# Power.net
KiCad netlist of a schematic drawn in Altium Designer
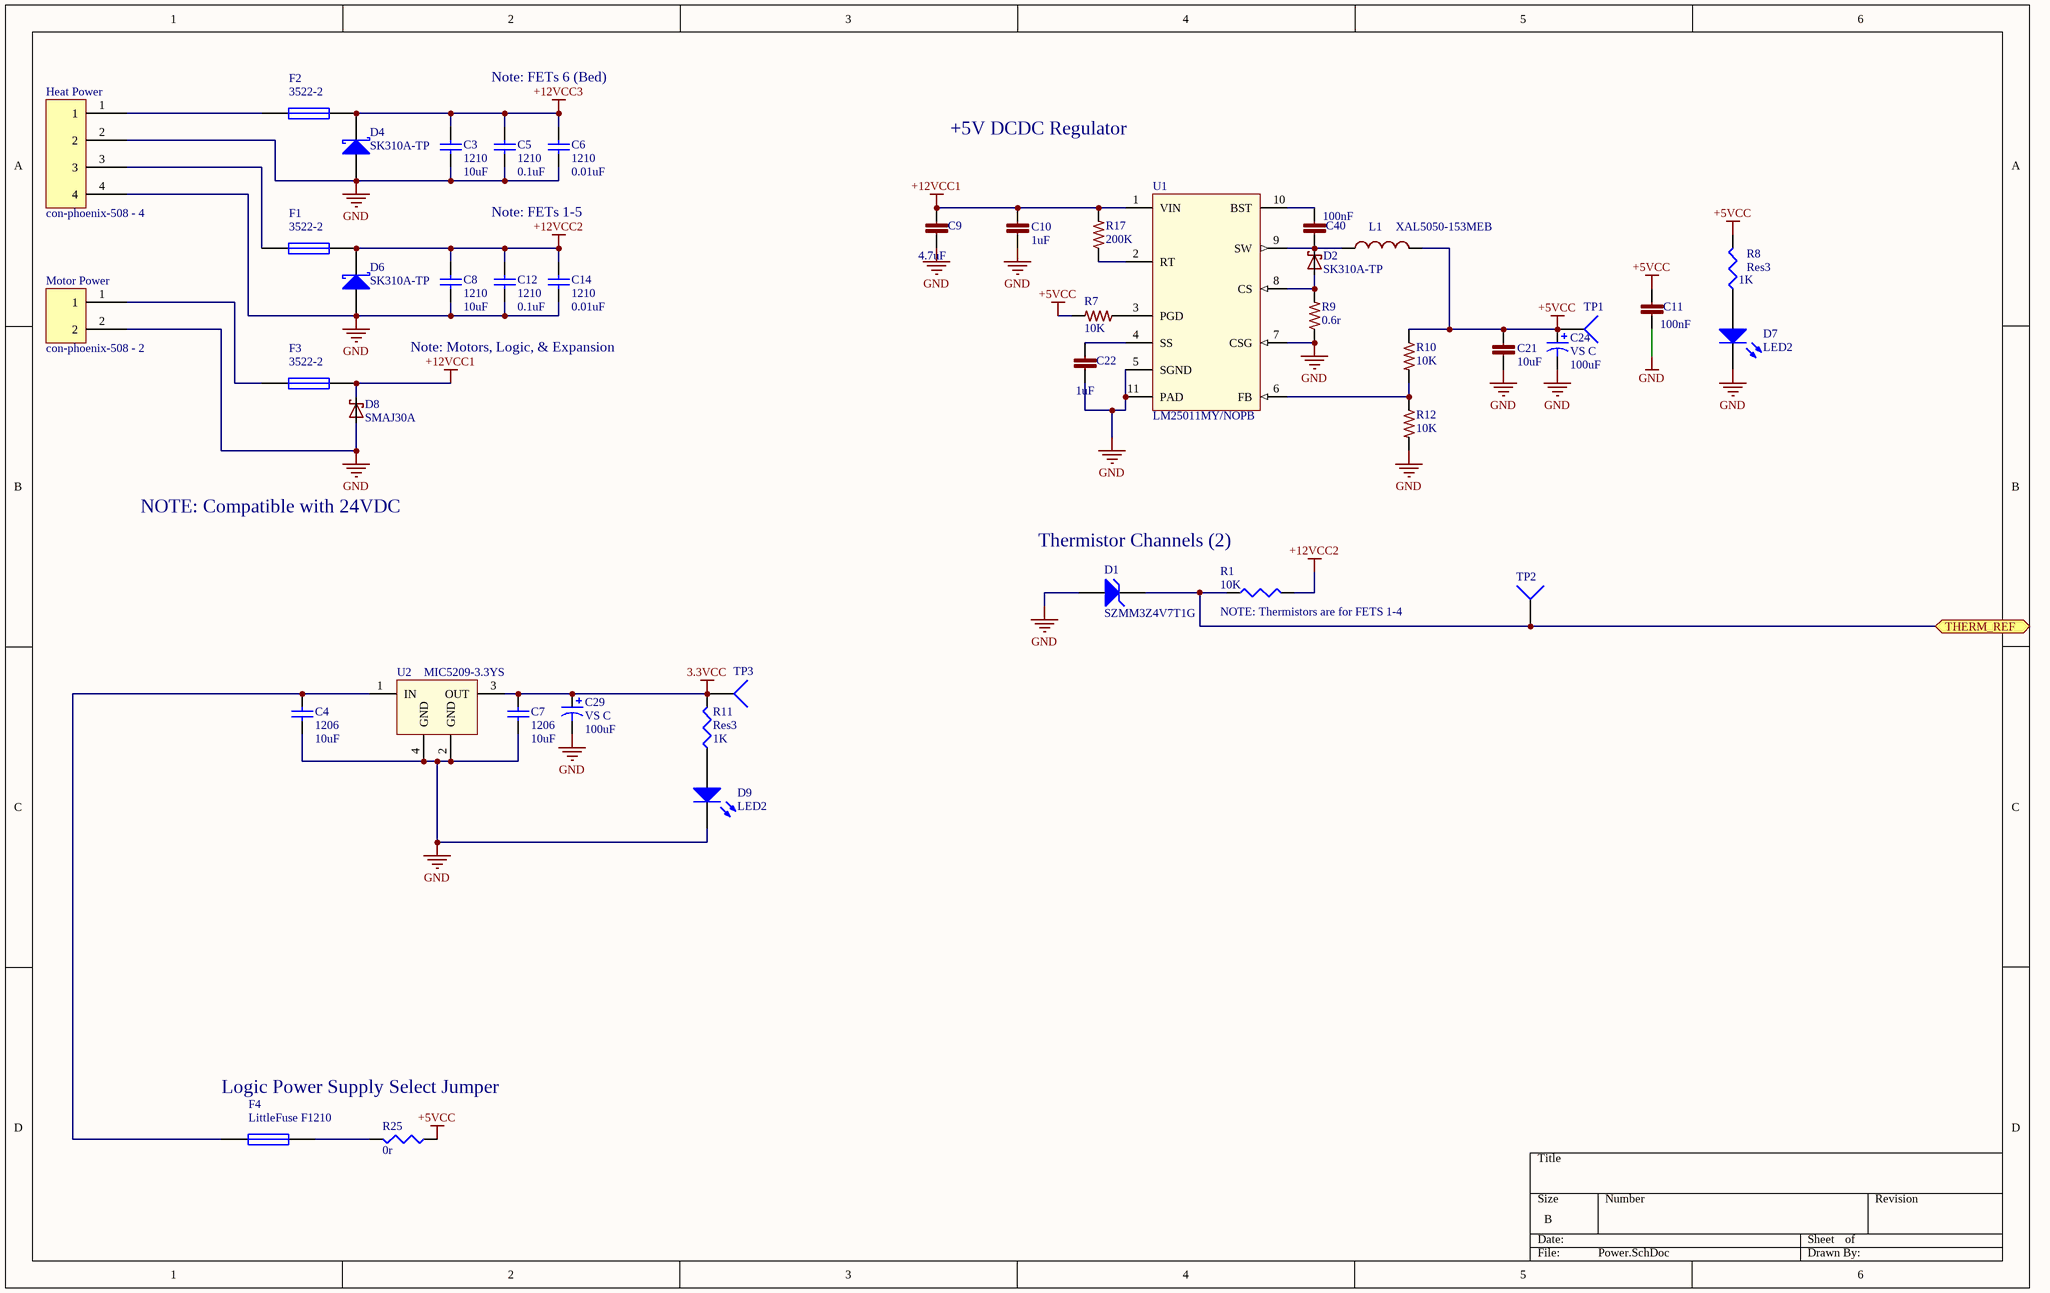
[diagram p0: Power.SchDoc]

(export (version "E")
  (design (tool "Eeschema 10.0.6"))
  (components
    (comp (ref "C3")
      (value "1210")
      (footprint "C1210")
      (description "Capacitor (Semiconductor SIM Model)")
      (fields (field (name "ALTIUM_VALUE") "10uF") (field (name "PUBLISHER") "Altium Limited"))
      (libsource (lib "Miscellaneous Devices") (part "Cap Semi"))
    )
    (comp (ref "C4")
      (value "1206")
      (footprint "C1206")
      (description "Capacitor (Semiconductor SIM Model)")
      (fields (field (name "ALTIUM_VALUE") "10uF") (field (name "PUBLISHER") "Altium Limited"))
      (libsource (lib "Miscellaneous Devices") (part "Cap Semi"))
    )
    (comp (ref "C5")
      (value "1210")
      (footprint "C1210")
      (description "Capacitor (Semiconductor SIM Model)")
      (fields (field (name "ALTIUM_VALUE") "0.1uF") (field (name "PUBLISHER") "Altium Limited"))
      (libsource (lib "Miscellaneous Devices") (part "Cap Semi"))
    )
    (comp (ref "C6")
      (value "1210")
      (footprint "C1210")
      (description "Capacitor (Semiconductor SIM Model)")
      (fields (field (name "ALTIUM_VALUE") "0.01uF") (field (name "PUBLISHER") "Altium Limited"))
      (libsource (lib "Miscellaneous Devices") (part "Cap Semi"))
    )
    (comp (ref "C7")
      (value "1206")
      (footprint "C1206")
      (description "Capacitor (Semiconductor SIM Model)")
      (fields (field (name "ALTIUM_VALUE") "10uF") (field (name "PUBLISHER") "Altium Limited"))
      (libsource (lib "Miscellaneous Devices") (part "Cap Semi"))
    )
    (comp (ref "C8")
      (value "1210")
      (footprint "C1210")
      (description "Capacitor (Semiconductor SIM Model)")
      (fields (field (name "ALTIUM_VALUE") "10uF") (field (name "PUBLISHER") "Altium Limited"))
      (libsource (lib "Miscellaneous Devices") (part "Cap Semi"))
    )
    (comp (ref "C9")
      (value "4.7uF")
      (footprint "C1206")
      (description "CAP CER 1206 4.7uF 50V 10% X5R")
      (fields
        (field (name "MANUFACTURERPARTNUMBER") "C1206C475K5PACTU")
        (field (name "PUBLISHER") "UltiMachine")
      )
      (libsource (lib "3Delight") (part "C1206C475K5PACTU"))
    )
    (comp (ref "C10")
      (value "1uF")
      (footprint "C0805")
      (description "CAP CER 0805 1uF 50V 10% X7R")
      (fields
        (field (name "MANUFACTURERPARTNUMBER") "GRM21BR71H105KA12L")
        (field (name "PUBLISHER") "UltiMachine")
      )
      (libsource (lib "3Delight") (part "GRM21BR71H105KA12L"))
    )
    (comp (ref "C11")
      (value "100nF")
      (footprint "C0603")
      (description "CAP CER 0603 100nF 50V 10% X7R")
      (fields
        (field (name "MANUFACTURERPARTNUMBER") "C0603C104K5RACTU")
        (field (name "PUBLISHER") "UltiMachine")
      )
      (libsource (lib "3Delight") (part "C0603C104K5RACTU"))
    )
    (comp (ref "C12")
      (value "1210")
      (footprint "C1210")
      (description "Capacitor (Semiconductor SIM Model)")
      (fields (field (name "ALTIUM_VALUE") "0.1uF") (field (name "PUBLISHER") "Altium Limited"))
      (libsource (lib "Miscellaneous Devices") (part "Cap Semi"))
    )
    (comp (ref "C14")
      (value "1210")
      (footprint "C1210")
      (description "Capacitor (Semiconductor SIM Model)")
      (fields (field (name "ALTIUM_VALUE") "0.01uF") (field (name "PUBLISHER") "Altium Limited"))
      (libsource (lib "Miscellaneous Devices") (part "Cap Semi"))
    )
    (comp (ref "C21")
      (value "10uF")
      (footprint "C0805")
      (description "CAP CER 0805 10uF 10V 10% X5R")
      (fields
        (field (name "MANUFACTURERPARTNUMBER") "C0805C106K8PACTU")
        (field (name "PUBLISHER") "UltiMachine")
      )
      (libsource (lib "3Delight") (part "C0805C106K8PACTU"))
    )
    (comp (ref "C22")
      (value "1uF")
      (footprint "C0402")
      (description "CAP CER 0402 1uF 6.3V 10% X5R")
      (fields
        (field (name "MANUFACTURERPARTNUMBER") "GRM155R60J105KE19D")
        (field (name "PUBLISHER") "UltiMachine")
      )
      (libsource (lib "3Delight") (part "GRM155R60J105KE19D"))
    )
    (comp (ref "C24")
      (value "VS C")
      (footprint "Panasonic VS C")
      (description "Polarized Capacitor (Surface Mount)")
      (fields (field (name "ALTIUM_VALUE") "100uF") (field (name "PUBLISHER") "Altium Limited"))
      (libsource (lib "Miscellaneous Devices") (part "Cap Pol3"))
    )
    (comp (ref "C29")
      (value "VS C")
      (footprint "Panasonic VS C")
      (description "Polarized Capacitor (Surface Mount)")
      (fields (field (name "ALTIUM_VALUE") "100uF") (field (name "PUBLISHER") "Altium Limited"))
      (libsource (lib "Miscellaneous Devices") (part "Cap Pol3"))
    )
    (comp (ref "C40")
      (value "100nF")
      (footprint "C0603")
      (description "CAP CER 0603 100nF 50V 10% X7R")
      (fields
        (field (name "MANUFACTURERPARTNUMBER") "C0603C104K5RACTU")
        (field (name "PUBLISHER") "UltiMachine")
      )
      (libsource (lib "3Delight") (part "C0603C104K5RACTU"))
    )
    (comp (ref "D1")
      (value "SZMM3Z4V7T1G")
      (footprint "SZMM3Z4V7T1G")
      (description "Zener Diode")
      (fields (field (name "PUBLISHER") "Altium Limited"))
      (libsource (lib "Miscellaneous Devices") (part "D Zener"))
    )
    (comp (ref "D2")
      (value "SK310A-TP")
      (footprint "SMA-SM")
      (description "DIODE Schottky 3A SMA")
      (fields (field (name "MANUFACTURERPARTNUMBER") "SK310A") (field (name "PUBLISHER") "UltiMachine"))
      (libsource (lib "3Delight") (part "SK310A"))
    )
    (comp (ref "D4")
      (value "SK310A-TP")
      (footprint "SK310A-TP")
      (description "Schottky Diode")
      (fields (field (name "PUBLISHER") "Altium Limited"))
      (libsource (lib "Miscellaneous Devices") (part "D Schottky"))
    )
    (comp (ref "D6")
      (value "SK310A-TP")
      (footprint "SK310A-TP")
      (description "Schottky Diode")
      (fields (field (name "PUBLISHER") "Altium Limited"))
      (libsource (lib "Miscellaneous Devices") (part "D Schottky"))
    )
    (comp (ref "D7")
      (value "LED2")
      (footprint "SM 0805 polarized")
      (description "Typical RED, GREEN, YELLOW, AMBER GaAs LED")
      (fields (field (name "PUBLISHER") "Altium Limited"))
      (libsource (lib "Miscellaneous Devices") (part "LED2"))
    )
    (comp (ref "D8")
      (value "SMAJ30A")
      (footprint "SMA-SM")
      (description "DIODE TVS 30V SMA")
      (fields (field (name "PUBLISHER") "UltiMachine"))
      (libsource (lib "ZMBo Schematic Library") (part "SMAJ30A"))
    )
    (comp (ref "D9")
      (value "LED2")
      (footprint "SM 0805 polarized")
      (description "Typical RED, GREEN, YELLOW, AMBER GaAs LED")
      (fields (field (name "PUBLISHER") "Altium Limited"))
      (libsource (lib "Miscellaneous Devices") (part "LED2"))
    )
    (comp (ref "F1")
      (value "3522-2")
      (footprint "3522-2 - WAVE SOLDER")
      (description "Fuse")
      (fields (field (name "PUBLISHER") "Altium Limited"))
      (libsource (lib "Miscellaneous Devices") (part "Fuse 1"))
    )
    (comp (ref "F2")
      (value "3522-2")
      (footprint "3522-2 - WAVE SOLDER")
      (description "Fuse")
      (fields (field (name "PUBLISHER") "Altium Limited"))
      (libsource (lib "Miscellaneous Devices") (part "Fuse 1"))
    )
    (comp (ref "F3")
      (value "3522-2")
      (footprint "3522-2 - WAVE SOLDER")
      (description "Fuse")
      (fields (field (name "PUBLISHER") "Altium Limited"))
      (libsource (lib "Miscellaneous Devices") (part "Fuse 1"))
    )
    (comp (ref "F4")
      (value "LittleFuse F1210")
      (footprint "F1210_M")
      (description "Fuse")
      (fields (field (name "PUBLISHER") "Altium Limited"))
      (libsource (lib "Miscellaneous Devices") (part "Fuse 1"))
    )
    (comp (ref "Heat Power")
      (value "con-phoenix-508 - 4")
      (footprint "MSTBV4")
      (libsource (lib "ZMBo Schematic Library") (part "con-phoenix-508_4"))
    )
    (comp (ref "L1")
      (value "XAL5050-153MEB")
      (footprint "XAL50xx-153")
      (description "IND 15uH 3.9A 20%")
      (fields (field (name "PUBLISHER") "UltiMachine"))
      (libsource (lib "3Delight") (part "XAL5050-153MEB"))
    )
    (comp (ref "Motor Power")
      (value "con-phoenix-508 - 2")
      (footprint "MSTBV2 - duplicate")
      (libsource (lib "ZMBo Schematic Library") (part "con-phoenix-508_2"))
    )
    (comp (ref "R1")
      (value "10K")
      (footprint "J1-0603")
      (description "Resistor")
      (fields (field (name "Comment") "Res3") (field (name "PUBLISHER") "Altium Limited"))
      (libsource (lib "Miscellaneous Devices") (part "Res3"))
    )
    (comp (ref "R7")
      (value "10K")
      (footprint "R0603")
      (description "RES 0603 10K 100mW 1%")
      (fields
        (field (name "MANUFACTURERPARTNUMBER") "ERJ-3EKF1002V")
        (field (name "PUBLISHER") "UltiMachine")
      )
      (libsource (lib "3Delight") (part "ERJ-3EKF1002V"))
    )
    (comp (ref "R8")
      (value "Res3")
      (footprint "SM 0805 - gap trimmed")
      (description "Resistor")
      (fields (field (name "ALTIUM_VALUE") "1K") (field (name "PUBLISHER") "Altium Limited"))
      (libsource (lib "Miscellaneous Devices") (part "Res3"))
    )
    (comp (ref "R9")
      (value "0.6r")
      (footprint "2512R-0.55")
      (description "RES 0.06 OHM 1W 1% 2512 SMD")
      (fields
        (field (name "MANUFACTURERPARTNUMBER") "RL2512FK-070R06L")
        (field (name "PUBLISHER") "UltiMachine")
      )
      (libsource (lib "3Delight") (part "RL2512FK-070R06L"))
    )
    (comp (ref "R10")
      (value "10K")
      (footprint "R0603")
      (description "RES 0603 10K 100mW 1%")
      (fields
        (field (name "MANUFACTURERPARTNUMBER") "ERJ-3EKF1002V")
        (field (name "PUBLISHER") "UltiMachine")
      )
      (libsource (lib "3Delight") (part "ERJ-3EKF1002V"))
    )
    (comp (ref "R11")
      (value "Res3")
      (footprint "SM 0805 - gap trimmed")
      (description "Resistor")
      (fields (field (name "ALTIUM_VALUE") "1K") (field (name "PUBLISHER") "Altium Limited"))
      (libsource (lib "Miscellaneous Devices") (part "Res3"))
    )
    (comp (ref "R12")
      (value "10K")
      (footprint "R0603")
      (description "RES 0603 10K 100mW 1%")
      (fields
        (field (name "MANUFACTURERPARTNUMBER") "ERJ-3EKF1002V")
        (field (name "PUBLISHER") "UltiMachine")
      )
      (libsource (lib "3Delight") (part "ERJ-3EKF1002V"))
    )
    (comp (ref "R17")
      (value "200K")
      (footprint "R0402")
      (description "RES 0402 22r 63mW 1%")
      (fields
        (field (name "MANUFACTURERPARTNUMBER") "CRCW0402200KFKED")
        (field (name "PUBLISHER") "UltiMachine")
      )
      (libsource (lib "3Delight") (part "CRCW0402200KFKED"))
    )
    (comp (ref "R25")
      (value "0r")
      (footprint "SM 0805 - gap trimmed")
      (description "Resistor")
      (fields (field (name "Comment") "Res3") (field (name "PUBLISHER") "Altium Limited"))
      (libsource (lib "Miscellaneous Devices") (part "Res3"))
    )
    (comp (ref "TP1")
      (value "TP4")
      (footprint "TP-2")
      (description "Socket")
      (fields (field (name "PUBLISHER") "Altium Limited"))
      (libsource (lib "ZMBo Schematic Library") (part "Socket"))
    )
    (comp (ref "TP2")
      (value "TP4")
      (footprint "TP-2")
      (description "Socket")
      (fields (field (name "PUBLISHER") "Altium Limited"))
      (libsource (lib "ZMBo Schematic Library") (part "Socket"))
    )
    (comp (ref "TP3")
      (value "TP4")
      (footprint "TP-2")
      (description "Socket")
      (fields (field (name "PUBLISHER") "Altium Limited"))
      (libsource (lib "ZMBo Schematic Library") (part "Socket"))
    )
    (comp (ref "U1")
      (value "LM25011MY/NOPB")
      (footprint "VSSOP10")
      (description "REG BUCK")
      (libsource (lib "3Delight") (part "LM25011"))
    )
    (comp (ref "U2")
      (value "MIC5209-3.3YS")
      (footprint "SOT230P700X190-4N")
      (libsource (lib "3Delight") (part "MIC5209-3.3YS"))
    )
  )
  (nets
    (net (code "1") (name "+5VCC") (class "Default")
      (node (ref "C11") (pin "1") (pinfunction "1_1") (pintype "passive"))
      (node (ref "C21") (pin "1") (pinfunction "1_1") (pintype "passive"))
      (node (ref "C24") (pin "1") (pinfunction "1_1") (pintype "passive"))
      (node (ref "L1") (pin "2") (pinfunction "2_2") (pintype "passive"))
      (node (ref "R10") (pin "1") (pinfunction "1_1") (pintype "passive"))
      (node (ref "R25") (pin "1") (pinfunction "1_1") (pintype "passive"))
      (node (ref "R7") (pin "2") (pinfunction "2_2") (pintype "passive"))
      (node (ref "R8") (pin "2") (pinfunction "2_2") (pintype "passive"))
      (node (ref "TP1") (pin "1") (pinfunction "1_1") (pintype "passive"))
    )
    (net (code "2") (name "+12VCC1") (class "Default")
      (node (ref "C10") (pin "1") (pinfunction "1_1") (pintype "passive"))
      (node (ref "C9") (pin "1") (pinfunction "1_1") (pintype "passive"))
      (node (ref "D8") (pin "C") (pinfunction "C_C") (pintype "passive"))
      (node (ref "F3") (pin "2") (pinfunction "2_2") (pintype "passive"))
      (node (ref "R17") (pin "2") (pinfunction "2_2") (pintype "passive"))
      (node (ref "U1") (pin "1") (pinfunction "VIN_1") (pintype "power_in"))
    )
    (net (code "3") (name "+12VCC2") (class "Default")
      (node (ref "C12") (pin "2") (pinfunction "2_2") (pintype "passive"))
      (node (ref "C14") (pin "2") (pinfunction "2_2") (pintype "passive"))
      (node (ref "C8") (pin "2") (pinfunction "2_2") (pintype "passive"))
      (node (ref "D6") (pin "2") (pinfunction "K_2") (pintype "passive"))
      (node (ref "F1") (pin "2") (pinfunction "2_2") (pintype "passive"))
      (node (ref "R1") (pin "2") (pinfunction "2_2") (pintype "passive"))
    )
    (net (code "4") (name "+12VCC3") (class "Default")
      (node (ref "C3") (pin "2") (pinfunction "2_2") (pintype "passive"))
      (node (ref "C5") (pin "2") (pinfunction "2_2") (pintype "passive"))
      (node (ref "C6") (pin "2") (pinfunction "2_2") (pintype "passive"))
      (node (ref "D4") (pin "2") (pinfunction "K_2") (pintype "passive"))
      (node (ref "F2") (pin "2") (pinfunction "2_2") (pintype "passive"))
    )
    (net (code "5") (name "/THERM_REF") (class "Default")
      (node (ref "D1") (pin "2") (pinfunction "K_2") (pintype "passive"))
      (node (ref "R1") (pin "1") (pinfunction "1_1") (pintype "passive"))
      (node (ref "TP2") (pin "1") (pinfunction "1_1") (pintype "passive"))
    )
    (net (code "6") (name "3.3VCC") (class "Default")
      (node (ref "C29") (pin "1") (pinfunction "1_1") (pintype "passive"))
      (node (ref "C7") (pin "2") (pinfunction "2_2") (pintype "passive"))
      (node (ref "R11") (pin "2") (pinfunction "2_2") (pintype "passive"))
      (node (ref "TP3") (pin "1") (pinfunction "1_1") (pintype "passive"))
      (node (ref "U2") (pin "3") (pinfunction "OUT_3") (pintype "power_in"))
    )
    (net (code "7") (name "GND") (class "Default")
      (node (ref "C10") (pin "2") (pinfunction "2_2") (pintype "passive"))
      (node (ref "C11") (pin "2") (pinfunction "2_2") (pintype "passive"))
      (node (ref "C12") (pin "1") (pinfunction "1_1") (pintype "passive"))
      (node (ref "C14") (pin "1") (pinfunction "1_1") (pintype "passive"))
      (node (ref "C21") (pin "2") (pinfunction "2_2") (pintype "passive"))
      (node (ref "C22") (pin "2") (pinfunction "2_2") (pintype "passive"))
      (node (ref "C24") (pin "2") (pinfunction "2_2") (pintype "passive"))
      (node (ref "C29") (pin "2") (pinfunction "2_2") (pintype "passive"))
      (node (ref "C3") (pin "1") (pinfunction "1_1") (pintype "passive"))
      (node (ref "C4") (pin "1") (pinfunction "1_1") (pintype "passive"))
      (node (ref "C5") (pin "1") (pinfunction "1_1") (pintype "passive"))
      (node (ref "C6") (pin "1") (pinfunction "1_1") (pintype "passive"))
      (node (ref "C7") (pin "1") (pinfunction "1_1") (pintype "passive"))
      (node (ref "C8") (pin "1") (pinfunction "1_1") (pintype "passive"))
      (node (ref "C9") (pin "2") (pinfunction "2_2") (pintype "passive"))
      (node (ref "D1") (pin "1") (pinfunction "A_1") (pintype "passive"))
      (node (ref "D4") (pin "1") (pinfunction "A_1") (pintype "passive"))
      (node (ref "D6") (pin "1") (pinfunction "A_1") (pintype "passive"))
      (node (ref "D7") (pin "1") (pinfunction "A_1") (pintype "passive"))
      (node (ref "D8") (pin "A") (pinfunction "A_A") (pintype "passive"))
      (node (ref "D9") (pin "1") (pinfunction "A_1") (pintype "passive"))
      (node (ref "Heat Power") (pin "2") (pinfunction "2_2") (pintype "passive"))
      (node (ref "Heat Power") (pin "4") (pinfunction "4_4") (pintype "passive"))
      (node (ref "Motor Power") (pin "2") (pinfunction "2_2") (pintype "passive"))
      (node (ref "R12") (pin "2") (pinfunction "2_2") (pintype "passive"))
      (node (ref "R9") (pin "1") (pinfunction "1_1") (pintype "passive"))
      (node (ref "U1") (pin "11") (pinfunction "PAD_11") (pintype "power_in"))
      (node (ref "U1") (pin "5") (pinfunction "SGND_5") (pintype "power_in"))
      (node (ref "U1") (pin "7") (pinfunction "CSG_7") (pintype "input"))
      (node (ref "U2") (pin "2") (pinfunction "GND_2") (pintype "power_in"))
      (node (ref "U2") (pin "4") (pinfunction "GND_4") (pintype "power_in"))
    )
    (net (code "8") (name "Net-(D7-K)") (class "Default")
      (node (ref "D7") (pin "2") (pinfunction "K_2") (pintype "passive"))
      (node (ref "R8") (pin "1") (pinfunction "1_1") (pintype "passive"))
    )
    (net (code "9") (name "Net-(D9-K)") (class "Default")
      (node (ref "D9") (pin "2") (pinfunction "K_2") (pintype "passive"))
      (node (ref "R11") (pin "1") (pinfunction "1_1") (pintype "passive"))
    )
    (net (code "10") (name "Net-(F1-Pad1)") (class "Default")
      (node (ref "F1") (pin "1") (pinfunction "1_1") (pintype "passive"))
      (node (ref "Heat Power") (pin "3") (pinfunction "3_3") (pintype "passive"))
    )
    (net (code "11") (name "Net-(F2-Pad1)") (class "Default")
      (node (ref "F2") (pin "1") (pinfunction "1_1") (pintype "passive"))
      (node (ref "Heat Power") (pin "1") (pinfunction "1_1") (pintype "passive"))
    )
    (net (code "12") (name "Net-(F3-Pad1)") (class "Default")
      (node (ref "F3") (pin "1") (pinfunction "1_1") (pintype "passive"))
      (node (ref "Motor Power") (pin "1") (pinfunction "1_1") (pintype "passive"))
    )
    (net (code "13") (name "Net-(F4-Pad2)") (class "Default")
      (node (ref "F4") (pin "2") (pinfunction "2_2") (pintype "passive"))
      (node (ref "R25") (pin "2") (pinfunction "2_2") (pintype "passive"))
    )
    (net (code "14") (name "Net-(U1-BST)") (class "Default")
      (node (ref "C40") (pin "1") (pinfunction "1_1") (pintype "passive"))
      (node (ref "U1") (pin "10") (pinfunction "BST_10") (pintype "power_in"))
    )
    (net (code "15") (name "Net-(U1-CS)") (class "Default")
      (node (ref "D2") (pin "A") (pinfunction "A_A") (pintype "passive"))
      (node (ref "R9") (pin "2") (pinfunction "2_2") (pintype "passive"))
      (node (ref "U1") (pin "8") (pinfunction "CS_8") (pintype "input"))
    )
    (net (code "16") (name "Net-(U1-FB)") (class "Default")
      (node (ref "R10") (pin "2") (pinfunction "2_2") (pintype "passive"))
      (node (ref "R12") (pin "1") (pinfunction "1_1") (pintype "passive"))
      (node (ref "U1") (pin "6") (pinfunction "FB_6") (pintype "input"))
    )
    (net (code "17") (name "Net-(U1-PGD)") (class "Default")
      (node (ref "R7") (pin "1") (pinfunction "1_1") (pintype "passive"))
      (node (ref "U1") (pin "3") (pinfunction "PGD_3") (pintype "power_in"))
    )
    (net (code "18") (name "Net-(U1-RT)") (class "Default")
      (node (ref "R17") (pin "1") (pinfunction "1_1") (pintype "passive"))
      (node (ref "U1") (pin "2") (pinfunction "RT_2") (pintype "power_in"))
    )
    (net (code "19") (name "Net-(U1-SS)") (class "Default")
      (node (ref "C22") (pin "1") (pinfunction "1_1") (pintype "passive"))
      (node (ref "U1") (pin "4") (pinfunction "SS_4") (pintype "power_in"))
    )
    (net (code "20") (name "Net-(U1-SW)") (class "Default")
      (node (ref "C40") (pin "2") (pinfunction "2_2") (pintype "passive"))
      (node (ref "D2") (pin "C") (pinfunction "C_C") (pintype "passive"))
      (node (ref "L1") (pin "1") (pinfunction "1_1") (pintype "passive"))
      (node (ref "U1") (pin "9") (pinfunction "SW_9") (pintype "output"))
    )
    (net (code "21") (name "Net-(U2-IN)") (class "Default")
      (node (ref "C4") (pin "2") (pinfunction "2_2") (pintype "passive"))
      (node (ref "F4") (pin "1") (pinfunction "1_1") (pintype "passive"))
      (node (ref "U2") (pin "1") (pinfunction "IN_1") (pintype "power_in"))
    )
  )
)
